# SW3526.net
KiCad netlist of a schematic drawn in EasyEDA Pro
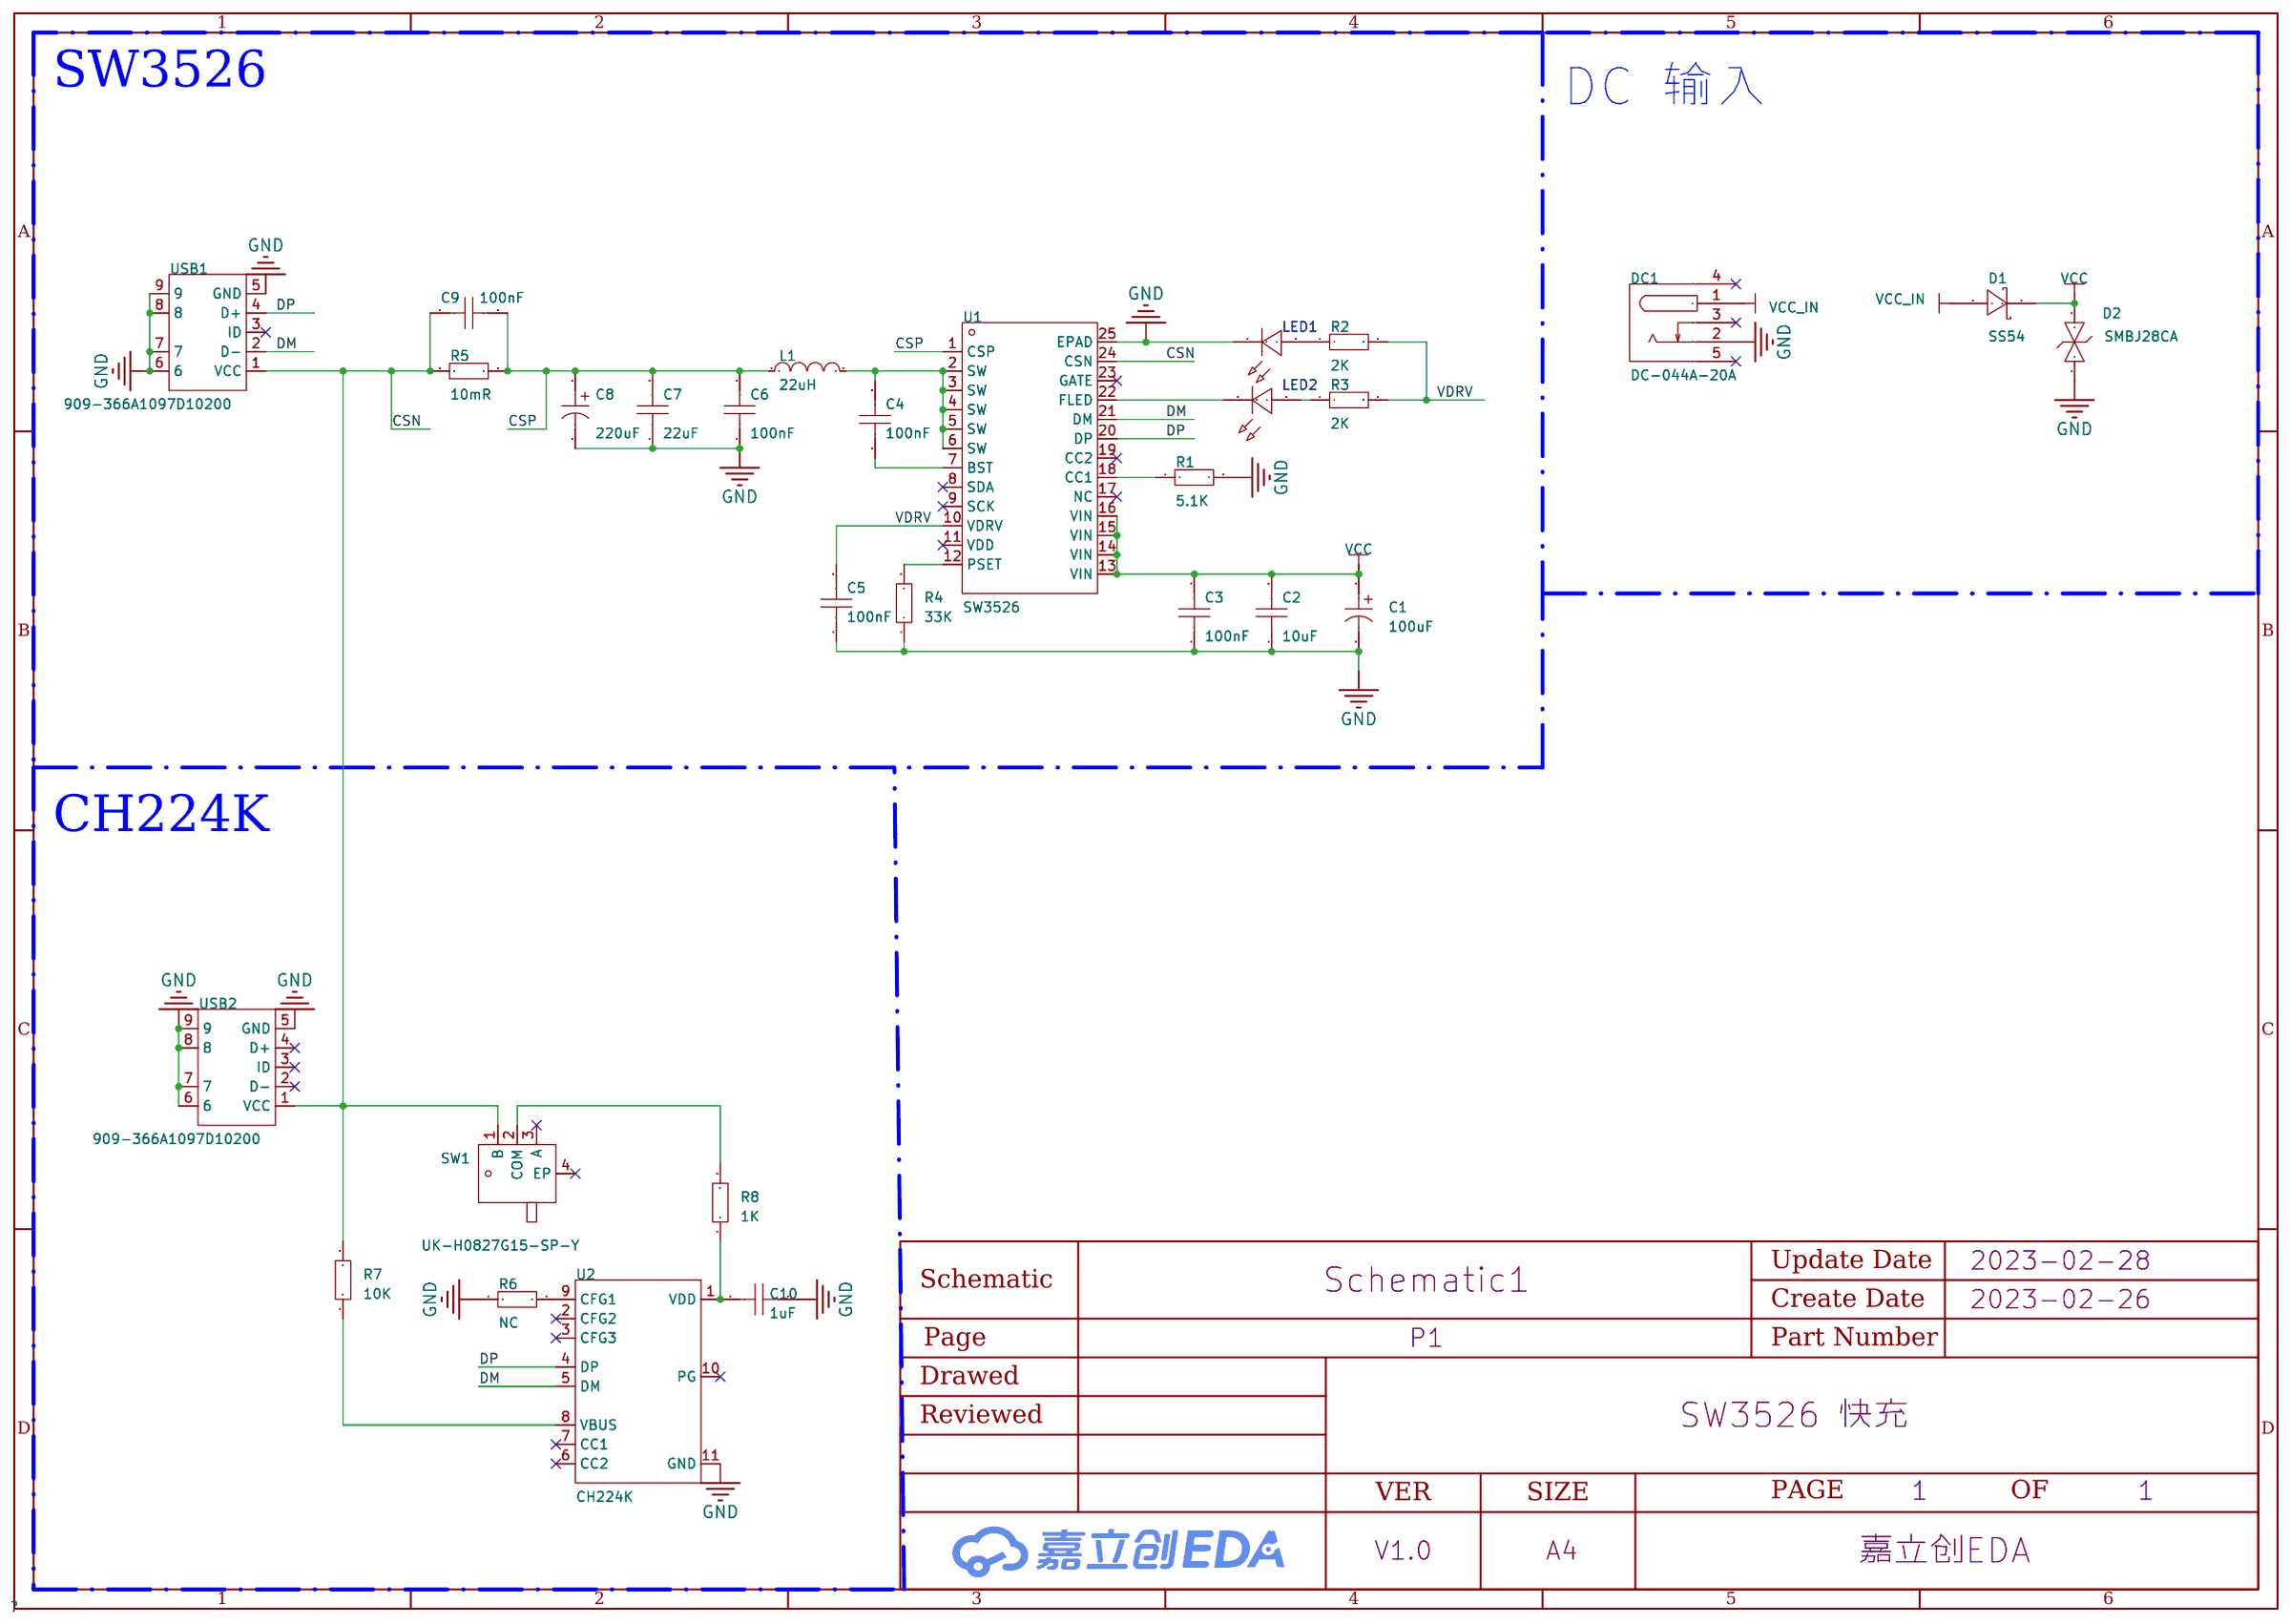
[diagram p0: schematic sheet]

(export (version "E")
  (design (tool "Eeschema 10.0.6"))
  (components
    (comp (ref "C1")
      (value "100uF")
      (footprint "easyedapro:CAP-TH_BD6.3-P2.50-D0.5-FD")
      (fields
        (field (name "Manufacturer Part") "PCR1VPF101MF08LL25WP")
        (field (name "Manufacturer") "Jianghai(南通江海)")
      )
      (libsource (lib "easyedapro") (part "PCR1VPF101MF08LL25WP"))
    )
    (comp (ref "C2")
      (value "10uF")
      (footprint "easyedapro:C0603")
      (libsource (lib "easyedapro") (part "CapAcitance"))
    )
    (comp (ref "C3")
      (value "100nF")
      (footprint "easyedapro:C0603")
      (libsource (lib "easyedapro") (part "CapAcitance"))
    )
    (comp (ref "C4")
      (value "100nF")
      (footprint "easyedapro:C0603")
      (libsource (lib "easyedapro") (part "CapAcitance"))
    )
    (comp (ref "C5")
      (value "100nF")
      (footprint "easyedapro:C0603")
      (libsource (lib "easyedapro") (part "CapAcitance"))
    )
    (comp (ref "C6")
      (value "100nF")
      (footprint "easyedapro:C0603")
      (libsource (lib "easyedapro") (part "CapAcitance"))
    )
    (comp (ref "C7")
      (value "22uF")
      (footprint "easyedapro:C0603")
      (libsource (lib "easyedapro") (part "CapAcitance"))
    )
    (comp (ref "C8")
      (value "220uF")
      (footprint "easyedapro:CAP-TH_BD8.0-P3.50-D0.6-FD-2")
      (fields
        (field (name "Manufacturer Part") "KNH2220UF35V149EC0049")
        (field (name "Manufacturer") "KNSCHA(科尼盛)")
      )
      (libsource (lib "easyedapro") (part "KNH2220UF35V149EC0049"))
    )
    (comp (ref "C9")
      (value "100nF")
      (footprint "easyedapro:C0603")
      (libsource (lib "easyedapro") (part "CapAcitance"))
    )
    (comp (ref "C10")
      (value "1uF")
      (footprint "easyedapro:C0603")
      (libsource (lib "easyedapro") (part "CapAcitance"))
    )
    (comp (ref "D1")
      (value "SS54")
      (footprint "easyedapro:SMA_L4.2-W2.6-LS5.3-RD")
      (fields (field (name "Manufacturer") "CJ(江苏长电/长晶)"))
      (libsource (lib "easyedapro") (part "SS54_C2929944"))
    )
    (comp (ref "D2")
      (value "SMBJ28CA")
      (footprint "easyedapro:SMB_L4.6-W3.6-LS5.3-BI")
      (description "极性:双向;")
      (fields (field (name "Manufacturer") "TWGMC(台湾迪嘉)"))
      (libsource (lib "easyedapro") (part "SMBJ28CA_C726872"))
    )
    (comp (ref "DC1")
      (value "DC-044A-20A")
      (footprint "easyedapro:DC-IN-TH_DC-044A-20A")
      (description "触点内径:2mm;触点外径:0.9mm;")
      (fields (field (name "Manufacturer") "韩国韩荣"))
      (libsource (lib "easyedapro") (part "DC-044A-20A"))
    )
    (comp (ref "L1")
      (value "22uH")
      (footprint "easyedapro:IND-SMD_L11.0-W10.0")
      (description "额定电流:5A;直流电阻(DCR):64mΩ;精度:±20%;电感值:22uH;")
      (fields
        (field (name "Manufacturer Part") "TMPC1004H-220MG-D")
        (field (name "Manufacturer") "TAI-TECH(台庆)")
      )
      (libsource (lib "easyedapro") (part "TMPC1004H-220MG-D"))
    )
    (comp (ref "LED1")
      (value "~")
      (footprint "easyedapro:LED_0805")
      (libsource (lib "easyedapro") (part "LED_G"))
    )
    (comp (ref "LED2")
      (value "~")
      (footprint "easyedapro:LED_0805")
      (libsource (lib "easyedapro") (part "LED_G"))
    )
    (comp (ref "R1") (value "5.1K") (footprint "easyedapro:R1206") (libsource (lib "easyedapro") (part "电阻")))
    (comp (ref "R2") (value "2K") (footprint "easyedapro:R1206") (libsource (lib "easyedapro") (part "电阻")))
    (comp (ref "R3") (value "2K") (footprint "easyedapro:R1206") (libsource (lib "easyedapro") (part "电阻")))
    (comp (ref "R4") (value "33K") (footprint "easyedapro:R1206") (libsource (lib "easyedapro") (part "电阻")))
    (comp (ref "R5") (value "10mR") (footprint "easyedapro:R1206") (libsource (lib "easyedapro") (part "电阻")))
    (comp (ref "R6") (value "NC") (footprint "easyedapro:R1206") (libsource (lib "easyedapro") (part "电阻")))
    (comp (ref "R7") (value "10K") (footprint "easyedapro:R1206") (libsource (lib "easyedapro") (part "电阻")))
    (comp (ref "R8") (value "1K") (footprint "easyedapro:R1206") (libsource (lib "easyedapro") (part "电阻")))
    (comp (ref "SW1")
      (value "UK-H0827G15-SP-Y")
      (footprint "easyedapro:SW-SMD_UK-H0827G15-SP-Y")
      (description "电路结构:-;开关功能:-;额定电压 DC:-;触点额定电流:-;额定电压 AC:-;")
      (fields (field (name "Manufacturer") "USAKRO(美韩)"))
      (libsource (lib "easyedapro") (part "UK-H0827G15-SP-Y"))
    )
    (comp (ref "U1")
      (value "SW3526")
      (footprint "easyedapro:QFN-24_L4.0-W4.0-P0.50-TL-EP2.5")
      (libsource (lib "easyedapro") (part "SW3526"))
    )
    (comp (ref "U2")
      (value "CH224K")
      (footprint "easyedapro:ESSOP-10_L4.9-W3.9-P1.0-LS6.0-TL-EP")
      (description "应用功能:USB充电芯片;")
      (fields (field (name "Manufacturer") "WCH(南京沁恒)"))
      (libsource (lib "easyedapro") (part "CH224K"))
    )
    (comp (ref "USB1")
      (value "909-366A1097D10200")
      (footprint "easyedapro:USB-A-TH_C168724")
      (description "连接器类型:Type-A;标准:USB 2.0;公母:母座;触点数量:5;端口数量:1;")
      (fields (field (name "Manufacturer") "精拓金"))
      (libsource (lib "easyedapro") (part "UAB-A-F-90-5P-H5.72"))
    )
    (comp (ref "USB2")
      (value "909-366A1097D10200")
      (footprint "easyedapro:USB-A-TH_C168724")
      (description "连接器类型:Type-A;标准:USB 2.0;公母:母座;触点数量:5;端口数量:1;")
      (fields (field (name "Manufacturer") "精拓金"))
      (libsource (lib "easyedapro") (part "UAB-A-F-90-5P-H5.72"))
    )
  )
  (nets
    (net (code "1") (name "/CSN") (class "Default")
      (node (ref "C9") (pin "1") (pinfunction "1_1") (pintype "input"))
      (node (ref "R5") (pin "1") (pinfunction "1_1") (pintype "input"))
      (node (ref "R7") (pin "2") (pinfunction "2_2") (pintype "input"))
      (node (ref "SW1") (pin "1") (pinfunction "B_1") (pintype "input"))
      (node (ref "U1") (pin "24") (pinfunction "CSN_24") (pintype "input"))
      (node (ref "USB1") (pin "1") (pinfunction "VCC_1") (pintype "input"))
      (node (ref "USB2") (pin "1") (pinfunction "VCC_1") (pintype "input"))
    )
    (net (code "2") (name "/CSP") (class "Default")
      (node (ref "C6") (pin "2") (pinfunction "2_2") (pintype "input"))
      (node (ref "C7") (pin "2") (pinfunction "2_2") (pintype "input"))
      (node (ref "C8") (pin "1") (pinfunction "1_1") (pintype "input"))
      (node (ref "C9") (pin "2") (pinfunction "2_2") (pintype "input"))
      (node (ref "L1") (pin "1") (pinfunction "1_1") (pintype "input"))
      (node (ref "R5") (pin "2") (pinfunction "2_2") (pintype "input"))
      (node (ref "U1") (pin "1") (pinfunction "CSP_1") (pintype "input"))
    )
    (net (code "3") (name "/DM") (class "Default")
      (node (ref "U1") (pin "21") (pinfunction "DM_21") (pintype "input"))
      (node (ref "U2") (pin "5") (pinfunction "DM_5") (pintype "input"))
      (node (ref "USB1") (pin "2") (pinfunction "D-_2") (pintype "input"))
    )
    (net (code "4") (name "/DP") (class "Default")
      (node (ref "U1") (pin "20") (pinfunction "DP_20") (pintype "input"))
      (node (ref "U2") (pin "4") (pinfunction "DP_4") (pintype "input"))
      (node (ref "USB1") (pin "4") (pinfunction "D+_4") (pintype "input"))
    )
    (net (code "5") (name "/VDRV") (class "Default")
      (node (ref "C5") (pin "2") (pinfunction "2_2") (pintype "input"))
      (node (ref "R2") (pin "2") (pinfunction "2_2") (pintype "input"))
      (node (ref "R3") (pin "2") (pinfunction "2_2") (pintype "input"))
      (node (ref "U1") (pin "10") (pinfunction "VDRV_10") (pintype "input"))
    )
    (net (code "6") (name "GND") (class "Default")
      (node (ref "C1") (pin "2") (pinfunction "2_2") (pintype "input"))
      (node (ref "C10") (pin "1") (pinfunction "1_1") (pintype "input"))
      (node (ref "C2") (pin "1") (pinfunction "1_1") (pintype "input"))
      (node (ref "C3") (pin "1") (pinfunction "1_1") (pintype "input"))
      (node (ref "C5") (pin "1") (pinfunction "1_1") (pintype "input"))
      (node (ref "C6") (pin "1") (pinfunction "1_1") (pintype "input"))
      (node (ref "C7") (pin "1") (pinfunction "1_1") (pintype "input"))
      (node (ref "C8") (pin "2") (pinfunction "2_2") (pintype "input"))
      (node (ref "D2") (pin "1") (pinfunction "1_1") (pintype "input"))
      (node (ref "DC1") (pin "2") (pinfunction "2_2") (pintype "input"))
      (node (ref "LED1") (pin "1") (pinfunction "C_1") (pintype "input"))
      (node (ref "R1") (pin "2") (pinfunction "2_2") (pintype "input"))
      (node (ref "R4") (pin "1") (pinfunction "1_1") (pintype "input"))
      (node (ref "R6") (pin "1") (pinfunction "1_1") (pintype "input"))
      (node (ref "U1") (pin "25") (pinfunction "EPAD_25") (pintype "input"))
      (node (ref "U2") (pin "11") (pinfunction "GND_11") (pintype "input"))
      (node (ref "USB1") (pin "5") (pinfunction "GND_5") (pintype "input"))
      (node (ref "USB1") (pin "6") (pinfunction "6_6") (pintype "input"))
      (node (ref "USB1") (pin "7") (pinfunction "7_7") (pintype "input"))
      (node (ref "USB1") (pin "8") (pinfunction "8_8") (pintype "input"))
      (node (ref "USB1") (pin "9") (pinfunction "9_9") (pintype "input"))
      (node (ref "USB2") (pin "5") (pinfunction "GND_5") (pintype "input"))
      (node (ref "USB2") (pin "6") (pinfunction "6_6") (pintype "input"))
      (node (ref "USB2") (pin "7") (pinfunction "7_7") (pintype "input"))
      (node (ref "USB2") (pin "8") (pinfunction "8_8") (pintype "input"))
      (node (ref "USB2") (pin "9") (pinfunction "9_9") (pintype "input"))
    )
    (net (code "7") (name "Net-(C4-Pad2)") (class "Default")
      (node (ref "C4") (pin "2") (pinfunction "2_2") (pintype "input"))
      (node (ref "L1") (pin "2") (pinfunction "2_2") (pintype "input"))
      (node (ref "U1") (pin "2") (pinfunction "SW_2") (pintype "input"))
      (node (ref "U1") (pin "3") (pinfunction "SW_3") (pintype "input"))
      (node (ref "U1") (pin "4") (pinfunction "SW_4") (pintype "input"))
      (node (ref "U1") (pin "5") (pinfunction "SW_5") (pintype "input"))
      (node (ref "U1") (pin "6") (pinfunction "SW_6") (pintype "input"))
    )
    (net (code "8") (name "Net-(LED1-A)") (class "Default")
      (node (ref "LED1") (pin "2") (pinfunction "A_2") (pintype "input"))
      (node (ref "R2") (pin "1") (pinfunction "1_1") (pintype "input"))
    )
    (net (code "9") (name "Net-(LED2-A)") (class "Default")
      (node (ref "LED2") (pin "2") (pinfunction "A_2") (pintype "input"))
      (node (ref "R3") (pin "1") (pinfunction "1_1") (pintype "input"))
    )
    (net (code "10") (name "Net-(LED2-C)") (class "Default")
      (node (ref "LED2") (pin "1") (pinfunction "C_1") (pintype "input"))
      (node (ref "U1") (pin "22") (pinfunction "FLED_22") (pintype "input"))
    )
    (net (code "11") (name "Net-(SW1-COM)") (class "Default")
      (node (ref "R8") (pin "2") (pinfunction "2_2") (pintype "input"))
      (node (ref "SW1") (pin "2") (pinfunction "COM_2") (pintype "input"))
    )
    (net (code "12") (name "Net-(U1-BST)") (class "Default")
      (node (ref "C4") (pin "1") (pinfunction "1_1") (pintype "input"))
      (node (ref "U1") (pin "7") (pinfunction "BST_7") (pintype "input"))
    )
    (net (code "13") (name "Net-(U1-CC1)") (class "Default")
      (node (ref "R1") (pin "1") (pinfunction "1_1") (pintype "input"))
      (node (ref "U1") (pin "18") (pinfunction "CC1_18") (pintype "input"))
    )
    (net (code "14") (name "Net-(U1-PSET)") (class "Default")
      (node (ref "R4") (pin "2") (pinfunction "2_2") (pintype "input"))
      (node (ref "U1") (pin "12") (pinfunction "PSET_12") (pintype "input"))
    )
    (net (code "15") (name "Net-(U2-CFG1)") (class "Default")
      (node (ref "R6") (pin "2") (pinfunction "2_2") (pintype "input"))
      (node (ref "U2") (pin "9") (pinfunction "CFG1_9") (pintype "input"))
    )
    (net (code "16") (name "Net-(U2-VBUS)") (class "Default")
      (node (ref "R7") (pin "1") (pinfunction "1_1") (pintype "input"))
      (node (ref "U2") (pin "8") (pinfunction "VBUS_8") (pintype "input"))
    )
    (net (code "17") (name "Net-(U2-VDD)") (class "Default")
      (node (ref "C10") (pin "2") (pinfunction "2_2") (pintype "input"))
      (node (ref "R8") (pin "1") (pinfunction "1_1") (pintype "input"))
      (node (ref "U2") (pin "1") (pinfunction "VDD_1") (pintype "input"))
    )
    (net (code "18") (name "VCC") (class "Default")
      (node (ref "C1") (pin "1") (pinfunction "1_1") (pintype "input"))
      (node (ref "C2") (pin "2") (pinfunction "2_2") (pintype "input"))
      (node (ref "C3") (pin "2") (pinfunction "2_2") (pintype "input"))
      (node (ref "D1") (pin "1") (pinfunction "C_1") (pintype "input"))
      (node (ref "D2") (pin "2") (pinfunction "2_2") (pintype "input"))
      (node (ref "U1") (pin "13") (pinfunction "VIN_13") (pintype "input"))
      (node (ref "U1") (pin "14") (pinfunction "VIN_14") (pintype "input"))
      (node (ref "U1") (pin "15") (pinfunction "VIN_15") (pintype "input"))
      (node (ref "U1") (pin "16") (pinfunction "VIN_16") (pintype "input"))
    )
    (net (code "19") (name "VCC_IN") (class "Default")
      (node (ref "D1") (pin "2") (pinfunction "A_2") (pintype "input"))
      (node (ref "DC1") (pin "1") (pinfunction "1_1") (pintype "input"))
    )
    (net (code "20") (name "unconnected-(DC1-Pad3)") (class "Default")
      (node (ref "DC1") (pin "3") (pinfunction "3_3") (pintype "input+no_connect"))
    )
    (net (code "21") (name "unconnected-(DC1-Pad4)") (class "Default")
      (node (ref "DC1") (pin "4") (pinfunction "4_4") (pintype "input+no_connect"))
    )
    (net (code "22") (name "unconnected-(DC1-Pad5)") (class "Default")
      (node (ref "DC1") (pin "5") (pinfunction "5_5") (pintype "input+no_connect"))
    )
    (net (code "23") (name "unconnected-(SW1-A-Pad3)") (class "Default")
      (node (ref "SW1") (pin "3") (pinfunction "A_3") (pintype "input+no_connect"))
    )
    (net (code "24") (name "unconnected-(SW1-EP-Pad4)") (class "Default")
      (node (ref "SW1") (pin "4") (pinfunction "EP_4") (pintype "input+no_connect"))
    )
    (net (code "25") (name "unconnected-(U1-CC2-Pad19)") (class "Default")
      (node (ref "U1") (pin "19") (pinfunction "CC2_19") (pintype "input+no_connect"))
    )
    (net (code "26") (name "unconnected-(U1-GATE-Pad23)") (class "Default")
      (node (ref "U1") (pin "23") (pinfunction "GATE_23") (pintype "input+no_connect"))
    )
    (net (code "27") (name "unconnected-(U1-NC-Pad17)") (class "Default")
      (node (ref "U1") (pin "17") (pinfunction "NC_17") (pintype "input+no_connect"))
    )
    (net (code "28") (name "unconnected-(U1-SCK-Pad9)") (class "Default")
      (node (ref "U1") (pin "9") (pinfunction "SCK_9") (pintype "input+no_connect"))
    )
    (net (code "29") (name "unconnected-(U1-SDA-Pad8)") (class "Default")
      (node (ref "U1") (pin "8") (pinfunction "SDA_8") (pintype "input+no_connect"))
    )
    (net (code "30") (name "unconnected-(U1-VDD-Pad11)") (class "Default")
      (node (ref "U1") (pin "11") (pinfunction "VDD_11") (pintype "input+no_connect"))
    )
    (net (code "31") (name "unconnected-(U2-CC1-Pad7)") (class "Default")
      (node (ref "U2") (pin "7") (pinfunction "CC1_7") (pintype "input+no_connect"))
    )
    (net (code "32") (name "unconnected-(U2-CC2-Pad6)") (class "Default")
      (node (ref "U2") (pin "6") (pinfunction "CC2_6") (pintype "input+no_connect"))
    )
    (net (code "33") (name "unconnected-(U2-CFG2-Pad2)") (class "Default")
      (node (ref "U2") (pin "2") (pinfunction "CFG2_2") (pintype "input+no_connect"))
    )
    (net (code "34") (name "unconnected-(U2-CFG3-Pad3)") (class "Default")
      (node (ref "U2") (pin "3") (pinfunction "CFG3_3") (pintype "input+no_connect"))
    )
    (net (code "35") (name "unconnected-(U2-PG-Pad10)") (class "Default")
      (node (ref "U2") (pin "10") (pinfunction "PG_10") (pintype "input+no_connect"))
    )
    (net (code "36") (name "unconnected-(USB1-ID-Pad3)") (class "Default")
      (node (ref "USB1") (pin "3") (pinfunction "ID_3") (pintype "input+no_connect"))
    )
    (net (code "37") (name "unconnected-(USB2-D+-Pad4)") (class "Default")
      (node (ref "USB2") (pin "4") (pinfunction "D+_4") (pintype "input+no_connect"))
    )
    (net (code "38") (name "unconnected-(USB2-D--Pad2)") (class "Default")
      (node (ref "USB2") (pin "2") (pinfunction "D-_2") (pintype "input+no_connect"))
    )
    (net (code "39") (name "unconnected-(USB2-ID-Pad3)") (class "Default")
      (node (ref "USB2") (pin "3") (pinfunction "ID_3") (pintype "input+no_connect"))
    )
  )
)
